# Reference.net
KiCad netlist of a schematic drawn in EAGLE
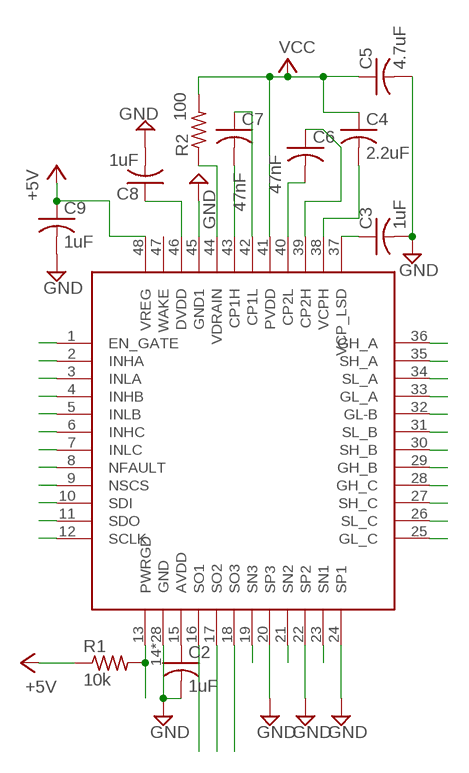
[diagram p0: schematic, sheet 1]

(export (version "E")
  (design (tool "Eeschema 10.0.6"))
  (components
    (comp (ref "C2")
      (value "1uF")
      (footprint "eagle-import:C0603")
      (libsource (lib "eagle-import") (part "C-USC0603"))
    )
    (comp (ref "C3")
      (value "1uF")
      (footprint "eagle-import:C0603")
      (libsource (lib "eagle-import") (part "C-USC0603"))
    )
    (comp (ref "C4")
      (value "2.2uF")
      (footprint "eagle-import:C0603")
      (libsource (lib "eagle-import") (part "C-USC0603"))
    )
    (comp (ref "C5")
      (value "4.7uF")
      (footprint "eagle-import:C0603")
      (libsource (lib "eagle-import") (part "C-USC0603"))
    )
    (comp (ref "C6")
      (value "47nF")
      (footprint "eagle-import:C0603")
      (libsource (lib "eagle-import") (part "C-USC0603"))
    )
    (comp (ref "C7")
      (value "47nF")
      (footprint "eagle-import:C0603")
      (libsource (lib "eagle-import") (part "C-USC0603"))
    )
    (comp (ref "C8")
      (value "1uF")
      (footprint "eagle-import:C0603")
      (libsource (lib "eagle-import") (part "C-USC0603"))
    )
    (comp (ref "C9")
      (value "1uF")
      (footprint "eagle-import:C0603")
      (libsource (lib "eagle-import") (part "C-USC0603"))
    )
    (comp (ref "R1")
      (value "10k")
      (footprint "eagle-import:R0603")
      (libsource (lib "eagle-import") (part "R-US_R0603"))
    )
    (comp (ref "R2")
      (value "100")
      (footprint "eagle-import:R0603")
      (libsource (lib "eagle-import") (part "R-US_R0603"))
    )
    (comp (ref "U$1")
      (value "DRV8305")
      (footprint "eagle-import:PFB_S-PQFP-G48")
      (libsource (lib "eagle-import") (part "DRV8305"))
    )
  )
  (nets
    (net (code "1") (name "+5V") (class "Default")
      (node (ref "C9") (pin "1") (pinfunction "1_1") (pintype "passive"))
      (node (ref "R1") (pin "1") (pinfunction "1_1") (pintype "passive"))
      (node (ref "U$1") (pin "48") (pinfunction "VREG_48") (pintype "bidirectional"))
    )
    (net (code "2") (name "/SL_A") (class "Default")
      (node (ref "U$1") (pin "23") (pinfunction "SN1_23") (pintype "bidirectional"))
      (node (ref "U$1") (pin "34") (pinfunction "SL_A_34") (pintype "bidirectional"))
    )
    (net (code "3") (name "/SL_B") (class "Default")
      (node (ref "U$1") (pin "21") (pinfunction "SN2_21") (pintype "bidirectional"))
      (node (ref "U$1") (pin "31") (pinfunction "SL_B_31") (pintype "bidirectional"))
    )
    (net (code "4") (name "/SL_C") (class "Default")
      (node (ref "U$1") (pin "19") (pinfunction "SN3_19") (pintype "bidirectional"))
      (node (ref "U$1") (pin "26") (pinfunction "SL_C_26") (pintype "bidirectional"))
    )
    (net (code "5") (name "GND") (class "Default")
      (node (ref "C2") (pin "2") (pinfunction "2_2") (pintype "passive"))
      (node (ref "C3") (pin "2") (pinfunction "2_2") (pintype "passive"))
      (node (ref "C5") (pin "2") (pinfunction "2_2") (pintype "passive"))
      (node (ref "C8") (pin "2") (pinfunction "2_2") (pintype "passive"))
      (node (ref "C9") (pin "2") (pinfunction "2_2") (pintype "passive"))
      (node (ref "U$1") (pin "14") (pinfunction "GND_14") (pintype "bidirectional"))
      (node (ref "U$1") (pin "20") (pinfunction "SP3_20") (pintype "bidirectional"))
      (node (ref "U$1") (pin "22") (pinfunction "SP2_22") (pintype "bidirectional"))
      (node (ref "U$1") (pin "24") (pinfunction "SP1_24") (pintype "bidirectional"))
      (node (ref "U$1") (pin "45") (pinfunction "GND1_45") (pintype "bidirectional"))
      (node (ref "U$1") (pin "P$1") (pinfunction "GND_P$1") (pintype "bidirectional"))
      (node (ref "U$1") (pin "P$10") (pinfunction "GND_P$10") (pintype "bidirectional"))
      (node (ref "U$1") (pin "P$11") (pinfunction "GND_P$11") (pintype "bidirectional"))
      (node (ref "U$1") (pin "P$12") (pinfunction "GND_P$12") (pintype "bidirectional"))
      (node (ref "U$1") (pin "P$13") (pinfunction "GND_P$13") (pintype "bidirectional"))
      (node (ref "U$1") (pin "P$14") (pinfunction "GND_P$14") (pintype "bidirectional"))
      (node (ref "U$1") (pin "P$15") (pinfunction "GND_P$15") (pintype "bidirectional"))
      (node (ref "U$1") (pin "P$16") (pinfunction "GND_P$16") (pintype "bidirectional"))
      (node (ref "U$1") (pin "P$17") (pinfunction "GND_P$17") (pintype "bidirectional"))
      (node (ref "U$1") (pin "P$18") (pinfunction "GND_P$18") (pintype "bidirectional"))
      (node (ref "U$1") (pin "P$19") (pinfunction "GND_P$19") (pintype "bidirectional"))
      (node (ref "U$1") (pin "P$2") (pinfunction "GND_P$2") (pintype "bidirectional"))
      (node (ref "U$1") (pin "P$20") (pinfunction "GND_P$20") (pintype "bidirectional"))
      (node (ref "U$1") (pin "P$21") (pinfunction "GND_P$21") (pintype "bidirectional"))
      (node (ref "U$1") (pin "P$22") (pinfunction "GND_P$22") (pintype "bidirectional"))
      (node (ref "U$1") (pin "P$23") (pinfunction "GND_P$23") (pintype "bidirectional"))
      (node (ref "U$1") (pin "P$24") (pinfunction "GND_P$24") (pintype "bidirectional"))
      (node (ref "U$1") (pin "P$25") (pinfunction "GND_P$25") (pintype "bidirectional"))
      (node (ref "U$1") (pin "P$26") (pinfunction "GND_P$26") (pintype "bidirectional"))
      (node (ref "U$1") (pin "P$27") (pinfunction "GND_P$27") (pintype "bidirectional"))
      (node (ref "U$1") (pin "P$3") (pinfunction "GND_P$3") (pintype "bidirectional"))
      (node (ref "U$1") (pin "P$4") (pinfunction "GND_P$4") (pintype "bidirectional"))
      (node (ref "U$1") (pin "P$5") (pinfunction "GND_P$5") (pintype "bidirectional"))
      (node (ref "U$1") (pin "P$6") (pinfunction "GND_P$6") (pintype "bidirectional"))
      (node (ref "U$1") (pin "P$7") (pinfunction "GND_P$7") (pintype "bidirectional"))
      (node (ref "U$1") (pin "P$8") (pinfunction "GND_P$8") (pintype "bidirectional"))
      (node (ref "U$1") (pin "P$9") (pinfunction "GND_P$9") (pintype "bidirectional"))
    )
    (net (code "6") (name "Net-(U$1-AVDD)") (class "Default")
      (node (ref "C2") (pin "1") (pinfunction "1_1") (pintype "passive"))
      (node (ref "U$1") (pin "15") (pinfunction "AVDD_15") (pintype "bidirectional"))
    )
    (net (code "7") (name "Net-(U$1-CP1H)") (class "Default")
      (node (ref "C7") (pin "2") (pinfunction "2_2") (pintype "passive"))
      (node (ref "U$1") (pin "43") (pinfunction "CP1H_43") (pintype "bidirectional"))
    )
    (net (code "8") (name "Net-(U$1-CP1L)") (class "Default")
      (node (ref "C7") (pin "1") (pinfunction "1_1") (pintype "passive"))
      (node (ref "U$1") (pin "42") (pinfunction "CP1L_42") (pintype "bidirectional"))
    )
    (net (code "9") (name "Net-(U$1-CP2H)") (class "Default")
      (node (ref "C6") (pin "1") (pinfunction "1_1") (pintype "passive"))
      (node (ref "U$1") (pin "39") (pinfunction "CP2H_39") (pintype "bidirectional"))
    )
    (net (code "10") (name "Net-(U$1-CP2L)") (class "Default")
      (node (ref "C6") (pin "2") (pinfunction "2_2") (pintype "passive"))
      (node (ref "U$1") (pin "40") (pinfunction "CP2L_40") (pintype "bidirectional"))
    )
    (net (code "11") (name "Net-(U$1-DVDD)") (class "Default")
      (node (ref "C8") (pin "1") (pinfunction "1_1") (pintype "passive"))
      (node (ref "U$1") (pin "46") (pinfunction "DVDD_46") (pintype "bidirectional"))
    )
    (net (code "12") (name "Net-(U$1-PWRGD)") (class "Default")
      (node (ref "R1") (pin "2") (pinfunction "2_2") (pintype "passive"))
      (node (ref "U$1") (pin "13") (pinfunction "PWRGD_13") (pintype "bidirectional"))
    )
    (net (code "13") (name "Net-(U$1-VCPH)") (class "Default")
      (node (ref "C4") (pin "2") (pinfunction "2_2") (pintype "passive"))
      (node (ref "U$1") (pin "38") (pinfunction "VCPH_38") (pintype "bidirectional"))
    )
    (net (code "14") (name "Net-(U$1-VCP_LSD)") (class "Default")
      (node (ref "C3") (pin "1") (pinfunction "1_1") (pintype "passive"))
      (node (ref "U$1") (pin "37") (pinfunction "VCP_LSD_37") (pintype "bidirectional"))
    )
    (net (code "15") (name "Net-(U$1-VDRAIN)") (class "Default")
      (node (ref "R2") (pin "1") (pinfunction "1_1") (pintype "passive"))
      (node (ref "U$1") (pin "44") (pinfunction "VDRAIN_44") (pintype "bidirectional"))
    )
    (net (code "16") (name "VCC") (class "Default")
      (node (ref "C4") (pin "1") (pinfunction "1_1") (pintype "passive"))
      (node (ref "C5") (pin "1") (pinfunction "1_1") (pintype "passive"))
      (node (ref "R2") (pin "2") (pinfunction "2_2") (pintype "passive"))
      (node (ref "U$1") (pin "41") (pinfunction "PVDD_41") (pintype "bidirectional"))
    )
    (net (code "17") (name "unconnected-(U$1-EN_GATE-Pad1)") (class "Default")
      (node (ref "U$1") (pin "1") (pinfunction "EN_GATE_1") (pintype "bidirectional"))
    )
    (net (code "18") (name "unconnected-(U$1-GH_A-Pad36)") (class "Default")
      (node (ref "U$1") (pin "36") (pinfunction "GH_A_36") (pintype "bidirectional"))
    )
    (net (code "19") (name "unconnected-(U$1-GH_B-Pad29)") (class "Default")
      (node (ref "U$1") (pin "29") (pinfunction "GH_B_29") (pintype "bidirectional"))
    )
    (net (code "20") (name "unconnected-(U$1-GH_C-Pad28)") (class "Default")
      (node (ref "U$1") (pin "28") (pinfunction "GH_C_28") (pintype "bidirectional"))
    )
    (net (code "21") (name "unconnected-(U$1-GL-B-Pad32)") (class "Default")
      (node (ref "U$1") (pin "32") (pinfunction "GL-B_32") (pintype "bidirectional"))
    )
    (net (code "22") (name "unconnected-(U$1-GL_A-Pad33)") (class "Default")
      (node (ref "U$1") (pin "33") (pinfunction "GL_A_33") (pintype "bidirectional"))
    )
    (net (code "23") (name "unconnected-(U$1-GL_C-Pad25)") (class "Default")
      (node (ref "U$1") (pin "25") (pinfunction "GL_C_25") (pintype "bidirectional"))
    )
    (net (code "24") (name "unconnected-(U$1-INHA-Pad2)") (class "Default")
      (node (ref "U$1") (pin "2") (pinfunction "INHA_2") (pintype "bidirectional"))
    )
    (net (code "25") (name "unconnected-(U$1-INHB-Pad4)") (class "Default")
      (node (ref "U$1") (pin "4") (pinfunction "INHB_4") (pintype "bidirectional"))
    )
    (net (code "26") (name "unconnected-(U$1-INHC-Pad6)") (class "Default")
      (node (ref "U$1") (pin "6") (pinfunction "INHC_6") (pintype "bidirectional"))
    )
    (net (code "27") (name "unconnected-(U$1-INLA-Pad3)") (class "Default")
      (node (ref "U$1") (pin "3") (pinfunction "INLA_3") (pintype "bidirectional"))
    )
    (net (code "28") (name "unconnected-(U$1-INLB-Pad5)") (class "Default")
      (node (ref "U$1") (pin "5") (pinfunction "INLB_5") (pintype "bidirectional"))
    )
    (net (code "29") (name "unconnected-(U$1-INLC-Pad7)") (class "Default")
      (node (ref "U$1") (pin "7") (pinfunction "INLC_7") (pintype "bidirectional"))
    )
    (net (code "30") (name "unconnected-(U$1-NFAULT-Pad8)") (class "Default")
      (node (ref "U$1") (pin "8") (pinfunction "NFAULT_8") (pintype "bidirectional"))
    )
    (net (code "31") (name "unconnected-(U$1-NSCS-Pad9)") (class "Default")
      (node (ref "U$1") (pin "9") (pinfunction "NSCS_9") (pintype "bidirectional"))
    )
    (net (code "32") (name "unconnected-(U$1-SCLK-Pad12)") (class "Default")
      (node (ref "U$1") (pin "12") (pinfunction "SCLK_12") (pintype "bidirectional"))
    )
    (net (code "33") (name "unconnected-(U$1-SDI-Pad10)") (class "Default")
      (node (ref "U$1") (pin "10") (pinfunction "SDI_10") (pintype "bidirectional"))
    )
    (net (code "34") (name "unconnected-(U$1-SDO-Pad11)") (class "Default")
      (node (ref "U$1") (pin "11") (pinfunction "SDO_11") (pintype "bidirectional"))
    )
    (net (code "35") (name "unconnected-(U$1-SH_A-Pad35)") (class "Default")
      (node (ref "U$1") (pin "35") (pinfunction "SH_A_35") (pintype "bidirectional"))
    )
    (net (code "36") (name "unconnected-(U$1-SH_B-Pad30)") (class "Default")
      (node (ref "U$1") (pin "30") (pinfunction "SH_B_30") (pintype "bidirectional"))
    )
    (net (code "37") (name "unconnected-(U$1-SH_C-Pad27)") (class "Default")
      (node (ref "U$1") (pin "27") (pinfunction "SH_C_27") (pintype "bidirectional"))
    )
    (net (code "38") (name "unconnected-(U$1-SO1-Pad16)") (class "Default")
      (node (ref "U$1") (pin "16") (pinfunction "SO1_16") (pintype "bidirectional"))
    )
    (net (code "39") (name "unconnected-(U$1-SO2-Pad17)") (class "Default")
      (node (ref "U$1") (pin "17") (pinfunction "SO2_17") (pintype "bidirectional"))
    )
    (net (code "40") (name "unconnected-(U$1-SO3-Pad18)") (class "Default")
      (node (ref "U$1") (pin "18") (pinfunction "SO3_18") (pintype "bidirectional"))
    )
    (net (code "41") (name "unconnected-(U$1-WAKE-Pad47)") (class "Default")
      (node (ref "U$1") (pin "47") (pinfunction "WAKE_47") (pintype "bidirectional"))
    )
  )
)
